# node_focuser.net
KiCad netlist of a schematic drawn in EAGLE
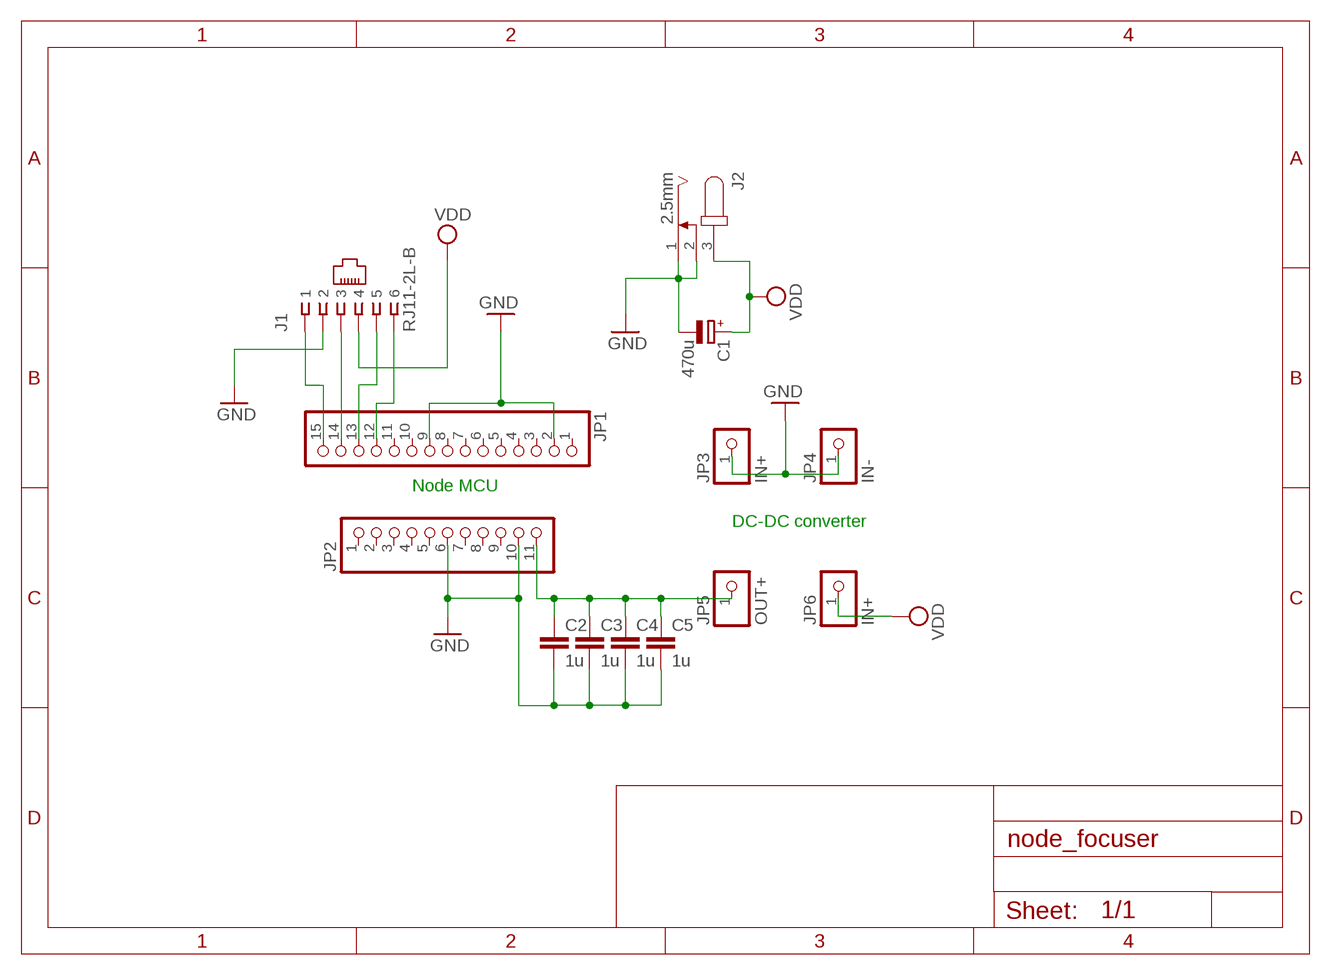
[diagram p0: schematic, sheet 1]

(export (version "E")
  (design (tool "Eeschema 10.0.6"))
  (components
    (comp (ref "C1")
      (value "470u")
      (footprint "eagle-import:E3,5-8")
      (libsource (lib "eagle-import") (part "CPOL-EUE3.5-8"))
    )
    (comp (ref "C2")
      (value "1u")
      (footprint "eagle-import:C5B3")
      (libsource (lib "eagle-import") (part "C5/3"))
    )
    (comp (ref "C3")
      (value "1u")
      (footprint "eagle-import:C5B3")
      (libsource (lib "eagle-import") (part "C5/3"))
    )
    (comp (ref "C4")
      (value "1u")
      (footprint "eagle-import:C5B3")
      (libsource (lib "eagle-import") (part "C5/3"))
    )
    (comp (ref "C5")
      (value "1u")
      (footprint "eagle-import:C5B3")
      (libsource (lib "eagle-import") (part "C5/3"))
    )
    (comp (ref "J1")
      (value "RJ11-2L-B")
      (footprint "eagle-import:RJ11-NO_SHIELD")
      (fields (field (name "MF") "TYCO ELECTRONICS"))
      (libsource (lib "eagle-import") (part "RJ11-2L-B"))
    )
    (comp (ref "J2")
      (value "2.5mm")
      (footprint "eagle-import:SPC4077")
      (libsource (lib "eagle-import") (part "JACK-PLUG0"))
    )
    (comp (ref "JP1")
      (value "PINHD-1X15")
      (footprint "eagle-import:1X15")
      (libsource (lib "eagle-import") (part "PINHD-1X15"))
    )
    (comp (ref "JP2")
      (value "PINHD-1X11")
      (footprint "eagle-import:1X11")
      (libsource (lib "eagle-import") (part "PINHD-1X11"))
    )
    (comp (ref "JP3")
      (value "IN+")
      (footprint "eagle-import:1X01")
      (libsource (lib "eagle-import") (part "PINHD-1X1"))
    )
    (comp (ref "JP4")
      (value "IN-")
      (footprint "eagle-import:1X01")
      (libsource (lib "eagle-import") (part "PINHD-1X1"))
    )
    (comp (ref "JP5")
      (value "OUT+")
      (footprint "eagle-import:1X01")
      (libsource (lib "eagle-import") (part "PINHD-1X1"))
    )
    (comp (ref "JP6")
      (value "IN+")
      (footprint "eagle-import:1X01")
      (libsource (lib "eagle-import") (part "PINHD-1X1"))
    )
  )
  (nets
    (net (code "1") (name "GND") (class "Default")
      (node (ref "C1") (pin "-") (pinfunction "-_-") (pintype "passive"))
      (node (ref "C2") (pin "2") (pinfunction "2_2") (pintype "passive"))
      (node (ref "C3") (pin "2") (pinfunction "2_2") (pintype "passive"))
      (node (ref "C4") (pin "2") (pinfunction "2_2") (pintype "passive"))
      (node (ref "C5") (pin "2") (pinfunction "2_2") (pintype "passive"))
      (node (ref "J1") (pin "2") (pinfunction "2_2") (pintype "passive"))
      (node (ref "J2") (pin "1") (pinfunction "1_1") (pintype "passive"))
      (node (ref "J2") (pin "2") (pinfunction "2_2") (pintype "passive"))
      (node (ref "JP1") (pin "2") (pinfunction "2_2") (pintype "passive"))
      (node (ref "JP1") (pin "9") (pinfunction "9_9") (pintype "passive"))
      (node (ref "JP2") (pin "10") (pinfunction "10_10") (pintype "passive"))
      (node (ref "JP2") (pin "6") (pinfunction "6_6") (pintype "passive"))
      (node (ref "JP3") (pin "1") (pinfunction "1_1") (pintype "passive"))
      (node (ref "JP4") (pin "1") (pinfunction "1_1") (pintype "passive"))
    )
    (net (code "2") (name "Net-(C2-Pad1)") (class "Default")
      (node (ref "C2") (pin "1") (pinfunction "1_1") (pintype "passive"))
      (node (ref "C3") (pin "1") (pinfunction "1_1") (pintype "passive"))
      (node (ref "C4") (pin "1") (pinfunction "1_1") (pintype "passive"))
      (node (ref "C5") (pin "1") (pinfunction "1_1") (pintype "passive"))
      (node (ref "JP2") (pin "11") (pinfunction "11_11") (pintype "passive"))
      (node (ref "JP5") (pin "1") (pinfunction "1_1") (pintype "passive"))
    )
    (net (code "3") (name "Net-(J1-Pad1)") (class "Default")
      (node (ref "J1") (pin "1") (pinfunction "1_1") (pintype "passive"))
      (node (ref "JP1") (pin "15") (pinfunction "15_15") (pintype "passive"))
    )
    (net (code "4") (name "Net-(J1-Pad3)") (class "Default")
      (node (ref "J1") (pin "3") (pinfunction "3_3") (pintype "passive"))
      (node (ref "JP1") (pin "14") (pinfunction "14_14") (pintype "passive"))
    )
    (net (code "5") (name "Net-(J1-Pad5)") (class "Default")
      (node (ref "J1") (pin "5") (pinfunction "5_5") (pintype "passive"))
      (node (ref "JP1") (pin "13") (pinfunction "13_13") (pintype "passive"))
    )
    (net (code "6") (name "Net-(J1-Pad6)") (class "Default")
      (node (ref "J1") (pin "6") (pinfunction "6_6") (pintype "passive"))
      (node (ref "JP1") (pin "12") (pinfunction "12_12") (pintype "passive"))
    )
    (net (code "7") (name "VDD") (class "Default")
      (node (ref "C1") (pin "+") (pinfunction "+_+") (pintype "passive"))
      (node (ref "J1") (pin "4") (pinfunction "4_4") (pintype "passive"))
      (node (ref "J2") (pin "3") (pinfunction "3_3") (pintype "passive"))
      (node (ref "JP6") (pin "1") (pinfunction "1_1") (pintype "passive"))
    )
    (net (code "8") (name "unconnected-(JP1-Pad1)") (class "Default")
      (node (ref "JP1") (pin "1") (pinfunction "1_1") (pintype "passive"))
    )
    (net (code "9") (name "unconnected-(JP1-Pad3)") (class "Default")
      (node (ref "JP1") (pin "3") (pinfunction "3_3") (pintype "passive"))
    )
    (net (code "10") (name "unconnected-(JP1-Pad4)") (class "Default")
      (node (ref "JP1") (pin "4") (pinfunction "4_4") (pintype "passive"))
    )
    (net (code "11") (name "unconnected-(JP1-Pad5)") (class "Default")
      (node (ref "JP1") (pin "5") (pinfunction "5_5") (pintype "passive"))
    )
    (net (code "12") (name "unconnected-(JP1-Pad6)") (class "Default")
      (node (ref "JP1") (pin "6") (pinfunction "6_6") (pintype "passive"))
    )
    (net (code "13") (name "unconnected-(JP1-Pad7)") (class "Default")
      (node (ref "JP1") (pin "7") (pinfunction "7_7") (pintype "passive"))
    )
    (net (code "14") (name "unconnected-(JP1-Pad8)") (class "Default")
      (node (ref "JP1") (pin "8") (pinfunction "8_8") (pintype "passive"))
    )
    (net (code "15") (name "unconnected-(JP1-Pad10)") (class "Default")
      (node (ref "JP1") (pin "10") (pinfunction "10_10") (pintype "passive"))
    )
    (net (code "16") (name "unconnected-(JP1-Pad11)") (class "Default")
      (node (ref "JP1") (pin "11") (pinfunction "11_11") (pintype "passive"))
    )
    (net (code "17") (name "unconnected-(JP2-Pad1)") (class "Default")
      (node (ref "JP2") (pin "1") (pinfunction "1_1") (pintype "passive"))
    )
    (net (code "18") (name "unconnected-(JP2-Pad2)") (class "Default")
      (node (ref "JP2") (pin "2") (pinfunction "2_2") (pintype "passive"))
    )
    (net (code "19") (name "unconnected-(JP2-Pad3)") (class "Default")
      (node (ref "JP2") (pin "3") (pinfunction "3_3") (pintype "passive"))
    )
    (net (code "20") (name "unconnected-(JP2-Pad4)") (class "Default")
      (node (ref "JP2") (pin "4") (pinfunction "4_4") (pintype "passive"))
    )
    (net (code "21") (name "unconnected-(JP2-Pad5)") (class "Default")
      (node (ref "JP2") (pin "5") (pinfunction "5_5") (pintype "passive"))
    )
    (net (code "22") (name "unconnected-(JP2-Pad7)") (class "Default")
      (node (ref "JP2") (pin "7") (pinfunction "7_7") (pintype "passive"))
    )
    (net (code "23") (name "unconnected-(JP2-Pad8)") (class "Default")
      (node (ref "JP2") (pin "8") (pinfunction "8_8") (pintype "passive"))
    )
    (net (code "24") (name "unconnected-(JP2-Pad9)") (class "Default")
      (node (ref "JP2") (pin "9") (pinfunction "9_9") (pintype "passive"))
    )
  )
)
